# phase_locked_loop.net
KiCad netlist of a schematic drawn in Altium Designer
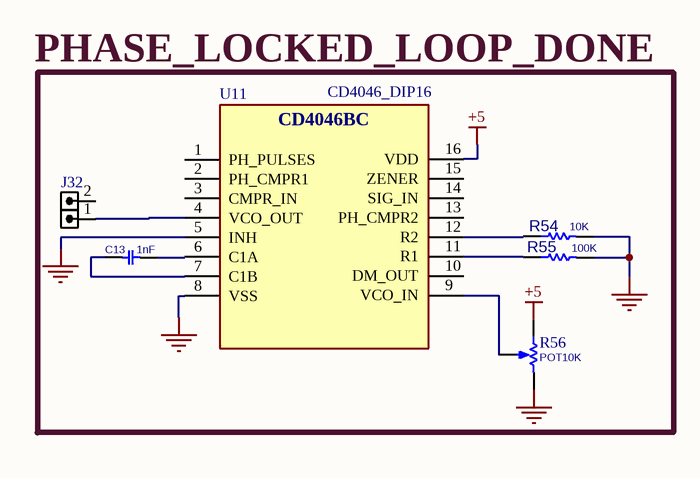
[diagram p0: phase_locked_loop.SchDoc]

(export (version "E")
  (design (tool "Eeschema 10.0.6"))
  (components
    (comp (ref "C13")
      (value "1nF")
      (footprint "C_CER_D3")
      (description "CAP, THD, CER MULTI LAYER,")
      (fields (field (name "MANF_P#") "MANF_PART#") (field (name "MANF") "MANF"))
      (libsource (lib "CapCer_passive") (part "CAP_THD_CERML"))
    )
    (comp (ref "J32")
      (value "HDRM2")
      (footprint "HDR_M_1X2")
      (description "CONN, HEADER, Male, pitch: 2.54mm, 2POS")
      (libsource (lib "conn_header_2.54mm_st") (part "HDR_M_1X2"))
    )
    (comp (ref "R54")
      (value "10K")
      (footprint "R025W_AX04")
      (description "RESISTOR, THD")
      (fields (field (name "MANF_P#") "RK73H1ETTP4701F") (field (name "MANF") "KOA SPEER"))
      (libsource (lib "passive_thd") (part "RES_THD"))
    )
    (comp (ref "R55")
      (value "100K")
      (footprint "R025W_AX04")
      (description "RESISTOR, THD")
      (fields (field (name "MANF_P#") "RK73H1ETTP4701F") (field (name "MANF") "KOA SPEER"))
      (libsource (lib "passive_thd") (part "RES_THD"))
    )
    (comp (ref "R56")
      (value "POT10K")
      (footprint "POT_3296W")
      (description "RESISTOR, THD, Potentiometer")
      (libsource (lib "resistor_pot_trimmer") (part "RES_THD_POT_3296W"))
    )
    (comp (ref "U11")
      (value "CD4046_DIP16")
      (footprint "DIP_16")
      (description "CREATED BY J / Micropower Phase-Locked Loop")
      (fields (field (name "MANF") "FAIRCHILD"))
      (libsource (lib "AvrDevelopmentBoard") (part "CD4046_DIP16"))
    )
  )
  (nets
    (net (code "1") (name "+5") (class "Default")
      (node (ref "R56") (pin "1") (pinfunction "TOP_1") (pintype "passive"))
      (node (ref "U11") (pin "16") (pinfunction "VDD_16") (pintype "passive"))
    )
    (net (code "2") (name "GND") (class "Default")
      (node (ref "R54") (pin "2") (pinfunction "2_2") (pintype "passive"))
      (node (ref "R55") (pin "2") (pinfunction "2_2") (pintype "passive"))
      (node (ref "R56") (pin "3") (pinfunction "BOT_3") (pintype "passive"))
      (node (ref "U11") (pin "5") (pinfunction "INH_5") (pintype "passive"))
      (node (ref "U11") (pin "8") (pinfunction "VSS_8") (pintype "passive"))
    )
    (net (code "3") (name "Net-(R56-TAP)") (class "Default")
      (node (ref "R56") (pin "2") (pinfunction "TAP_2") (pintype "passive"))
      (node (ref "U11") (pin "9") (pinfunction "VCO_IN_9") (pintype "passive"))
    )
    (net (code "4") (name "Net-(U11-C1A)") (class "Default")
      (node (ref "C13") (pin "2") (pinfunction "2_2") (pintype "passive"))
      (node (ref "U11") (pin "6") (pinfunction "C1A_6") (pintype "passive"))
    )
    (net (code "5") (name "Net-(U11-C1B)") (class "Default")
      (node (ref "C13") (pin "1") (pinfunction "1_1") (pintype "passive"))
      (node (ref "U11") (pin "7") (pinfunction "C1B_7") (pintype "passive"))
    )
    (net (code "6") (name "Net-(U11-R1)") (class "Default")
      (node (ref "R55") (pin "1") (pinfunction "1_1") (pintype "passive"))
      (node (ref "U11") (pin "11") (pinfunction "R1_11") (pintype "passive"))
    )
    (net (code "7") (name "Net-(U11-R2)") (class "Default")
      (node (ref "R54") (pin "1") (pinfunction "1_1") (pintype "passive"))
      (node (ref "U11") (pin "12") (pinfunction "R2_12") (pintype "passive"))
    )
    (net (code "8") (name "Net-(U11-VCO_OUT)") (class "Default")
      (node (ref "J32") (pin "1") (pinfunction "1_1") (pintype "passive"))
      (node (ref "U11") (pin "4") (pinfunction "VCO_OUT_4") (pintype "passive"))
    )
    (net (code "9") (name "unconnected-(J32-Pad2)") (class "Default")
      (node (ref "J32") (pin "2") (pinfunction "2_2") (pintype "passive"))
    )
    (net (code "10") (name "unconnected-(U11-CMPR_IN-Pad3)") (class "Default")
      (node (ref "U11") (pin "3") (pinfunction "CMPR_IN_3") (pintype "passive"))
    )
    (net (code "11") (name "unconnected-(U11-DM_OUT-Pad10)") (class "Default")
      (node (ref "U11") (pin "10") (pinfunction "DM_OUT_10") (pintype "passive"))
    )
    (net (code "12") (name "unconnected-(U11-PH_CMPR1-Pad2)") (class "Default")
      (node (ref "U11") (pin "2") (pinfunction "PH_CMPR1_2") (pintype "passive"))
    )
    (net (code "13") (name "unconnected-(U11-PH_CMPR2-Pad13)") (class "Default")
      (node (ref "U11") (pin "13") (pinfunction "PH_CMPR2_13") (pintype "passive"))
    )
    (net (code "14") (name "unconnected-(U11-PH_PULSES-Pad1)") (class "Default")
      (node (ref "U11") (pin "1") (pinfunction "PH_PULSES_1") (pintype "passive"))
    )
    (net (code "15") (name "unconnected-(U11-SIG_IN-Pad14)") (class "Default")
      (node (ref "U11") (pin "14") (pinfunction "SIG_IN_14") (pintype "passive"))
    )
    (net (code "16") (name "unconnected-(U11-ZENER-Pad15)") (class "Default")
      (node (ref "U11") (pin "15") (pinfunction "ZENER_15") (pintype "passive"))
    )
  )
)
